# Power_XC6220B_5V.net
KiCad netlist of a schematic drawn in Altium Designer
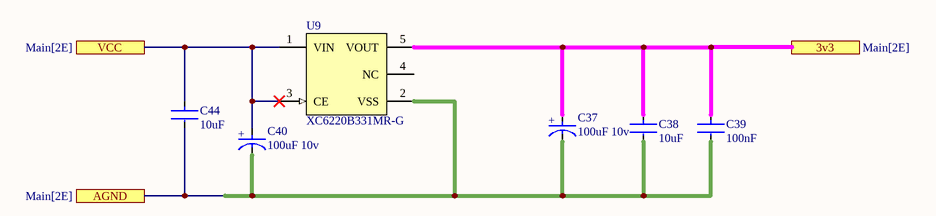
[diagram p0: Power_XC6220B_5V.SchDoc]

(export (version "E")
  (design (tool "Eeschema 10.0.6"))
  (components
    (comp (ref "C37")
      (value "100uF 10v")
      (footprint "Hosein_PCB_Lib_SMD:CAP-ALUM_5*5.4mm")
      (description "CAP ALUM SMD")
      (fields (field (name "TOLERANCE") "20%") (field (name "VOLTAGE") "35V"))
      (libsource (lib "Hosein_PCB_Lib") (part "CAP-ALUM"))
    )
    (comp (ref "C38")
      (value "10uF")
      (footprint "Hosein_PCB_Lib_SMD:CAP-0603")
      (description "Chip Multilayer Ceramic Capacitors for General Purpose, 0603")
      (fields (field (name "VOLTAGE") "6.3V") (field (name "TOLERANCE") "20%"))
      (libsource (lib "Hosein_PCB_Lib") (part "CAP-Ceramic"))
    )
    (comp (ref "C39")
      (value "100nF")
      (footprint "Hosein_PCB_Lib_SMD:CAP-0603")
      (description "Chip Multilayer Ceramic Capacitors for General Purpose, 0603")
      (fields (field (name "VOLTAGE") "6.3V") (field (name "TOLERANCE") "20%"))
      (libsource (lib "Hosein_PCB_Lib") (part "CAP-Ceramic"))
    )
    (comp (ref "C40")
      (value "100uF 10v")
      (footprint "Hosein_PCB_Lib_SMD:CAP-ALUM_5*5.4mm")
      (description "CAP ALUM SMD")
      (fields (field (name "TOLERANCE") "20%") (field (name "VOLTAGE") "35V"))
      (libsource (lib "Hosein_PCB_Lib") (part "CAP-ALUM"))
    )
    (comp (ref "C44")
      (value "10uF")
      (footprint "Hosein_PCB_Lib_SMD:CAP-0603")
      (description "Chip Multilayer Ceramic Capacitors for General Purpose, 0603")
      (fields (field (name "VOLTAGE") "6.3V") (field (name "TOLERANCE") "20%"))
      (libsource (lib "Hosein_PCB_Lib") (part "CAP-Ceramic"))
    )
    (comp (ref "U9")
      (value "XC6220B331MR-G")
      (footprint "TORX-SOT-25-5_M")
      (fields (field (name "MANUFACTURER") "Torex"))
      (libsource (lib "Altium Content Vault") (part "TORX-XC6220-SOT-25-5"))
    )
  )
  (nets
    (net (code "1") (name "/3v3") (class "Default")
      (node (ref "C37") (pin "2") (pinfunction "A_2") (pintype "passive"))
      (node (ref "C38") (pin "1") (pinfunction "1_1") (pintype "passive"))
      (node (ref "C39") (pin "1") (pinfunction "1_1") (pintype "passive"))
      (node (ref "U9") (pin "5") (pinfunction "VOUT_5") (pintype "power_in"))
    )
    (net (code "2") (name "/AGND") (class "Default")
      (node (ref "C37") (pin "1") (pinfunction "C_1") (pintype "passive"))
      (node (ref "C38") (pin "2") (pinfunction "2_2") (pintype "passive"))
      (node (ref "C39") (pin "2") (pinfunction "2_2") (pintype "passive"))
      (node (ref "C40") (pin "1") (pinfunction "C_1") (pintype "passive"))
      (node (ref "C44") (pin "2") (pinfunction "2_2") (pintype "passive"))
      (node (ref "U9") (pin "2") (pinfunction "VSS_2") (pintype "power_in"))
    )
    (net (code "3") (name "/VCC") (class "Default")
      (node (ref "C40") (pin "2") (pinfunction "A_2") (pintype "passive"))
      (node (ref "C44") (pin "1") (pinfunction "1_1") (pintype "passive"))
      (node (ref "U9") (pin "1") (pinfunction "VIN_1") (pintype "power_in"))
      (node (ref "U9") (pin "3") (pinfunction "CE_3") (pintype "input"))
    )
    (net (code "4") (name "unconnected-(U9-NC-Pad4)") (class "Default")
      (node (ref "U9") (pin "4") (pinfunction "NC_4") (pintype "passive"))
    )
  )
)
